# OLM-base_v0_2.net
KiCad netlist of a schematic drawn in EAGLE
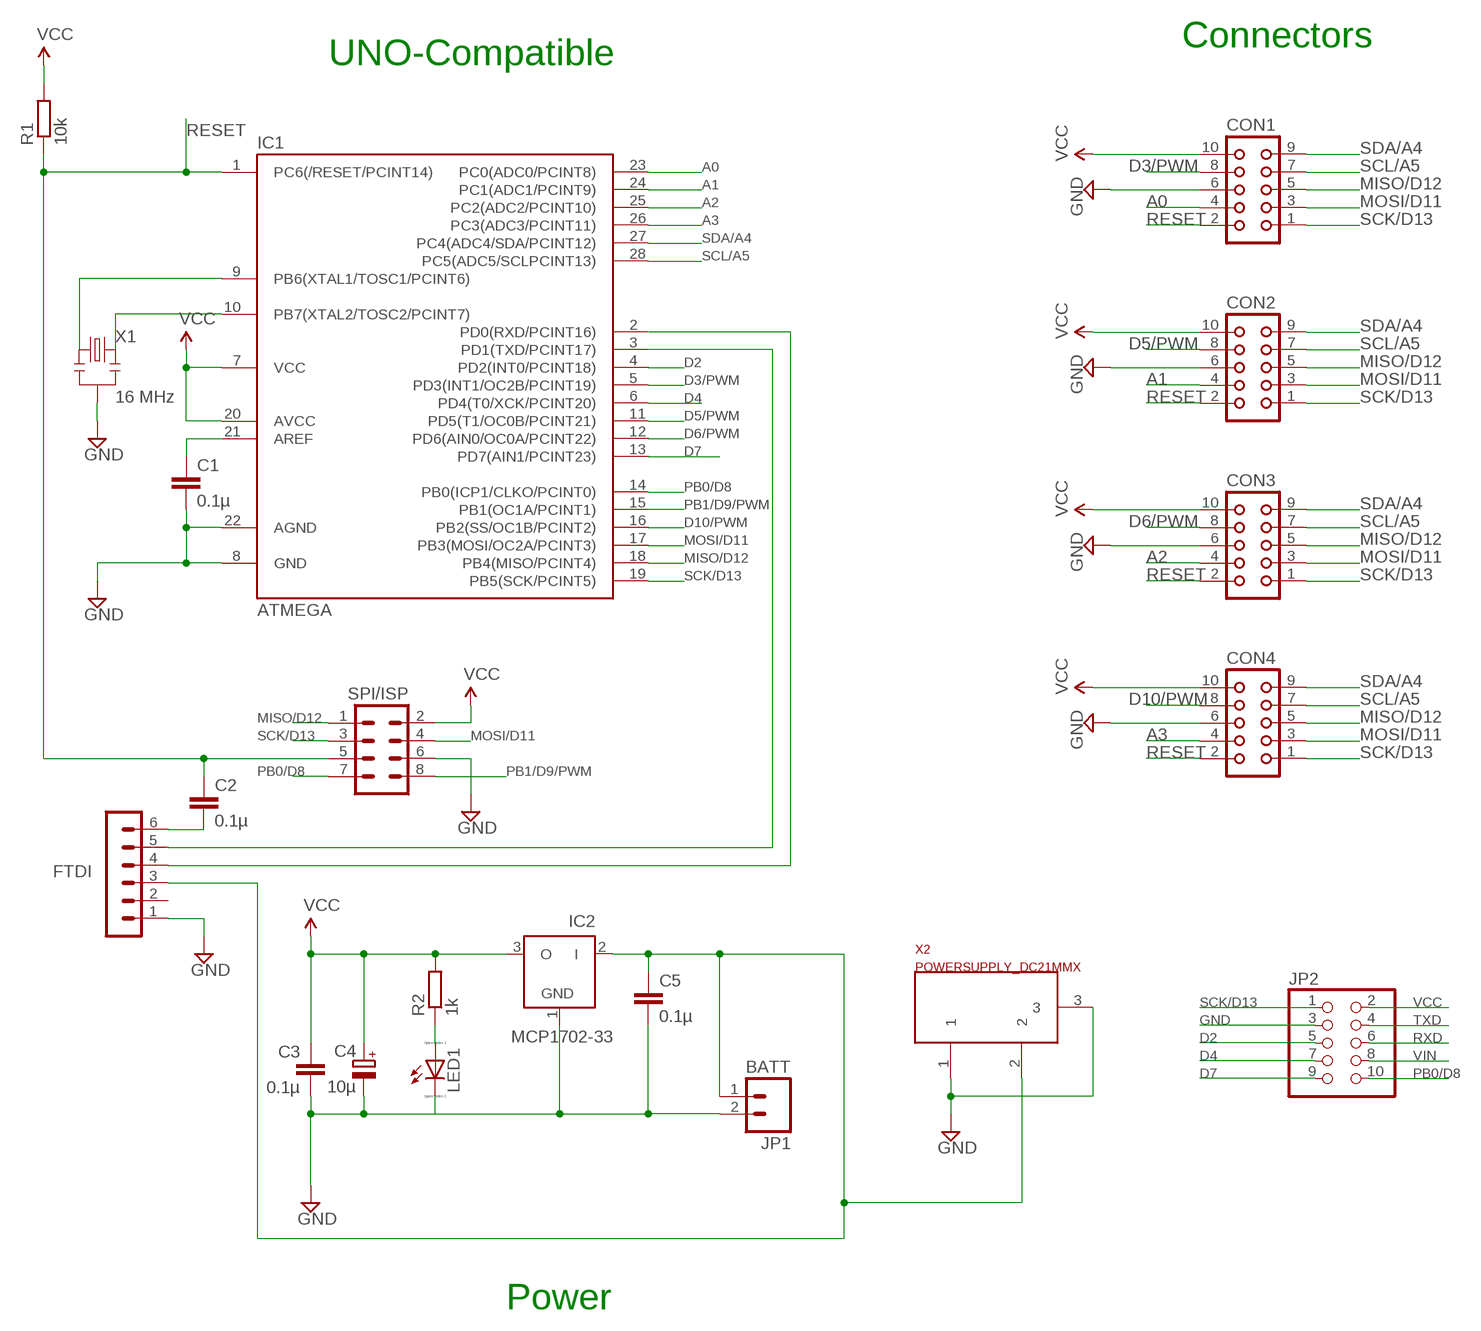
[diagram p0: schematic, sheet 1]

(export (version "E")
  (design (tool "Eeschema 10.0.6"))
  (components
    (comp (ref "C1")
      (value "0.1µ")
      (footprint "eagle-import:C025-024X044")
      (libsource (lib "eagle-import") (part "C-EU025-024X044"))
    )
    (comp (ref "C2")
      (value "0.1µ")
      (footprint "eagle-import:C025-024X044")
      (libsource (lib "eagle-import") (part "C-EU025-024X044"))
    )
    (comp (ref "C3")
      (value "0.1µ")
      (footprint "eagle-import:C025-024X044")
      (libsource (lib "eagle-import") (part "C-EU025-024X044"))
    )
    (comp (ref "C4")
      (value "10µ")
      (footprint "eagle-import:E1,8-4")
      (libsource (lib "eagle-import") (part "CPOL-EUE1.8-4"))
    )
    (comp (ref "C5")
      (value "0.1µ")
      (footprint "eagle-import:C025-024X044")
      (libsource (lib "eagle-import") (part "C-EU025-024X044"))
    )
    (comp (ref "CON1")
      (value "CON10L")
      (footprint "eagle-import:CON10L")
      (libsource (lib "eagle-import") (part "CON10L"))
    )
    (comp (ref "CON2")
      (value "CON10L")
      (footprint "eagle-import:CON10L")
      (libsource (lib "eagle-import") (part "CON10L"))
    )
    (comp (ref "CON3")
      (value "CON10L")
      (footprint "eagle-import:CON10L")
      (libsource (lib "eagle-import") (part "CON10L"))
    )
    (comp (ref "CON4")
      (value "CON10L")
      (footprint "eagle-import:CON10L")
      (libsource (lib "eagle-import") (part "CON10L"))
    )
    (comp (ref "FTDI")
      (value "FTDI")
      (footprint "eagle-import:MA06-1")
      (libsource (lib "eagle-import") (part "MA06-1"))
    )
    (comp (ref "IC1")
      (value "ATMEGA")
      (footprint "eagle-import:DIL28-3")
      (libsource (lib "eagle-import") (part "ATMEGA48/88/168-PU"))
    )
    (comp (ref "IC2")
      (value "MCP1702-33")
      (footprint "eagle-import:TO92")
      (libsource (lib "eagle-import") (part "MCP1702Z"))
    )
    (comp (ref "JP1")
      (value "BATT")
      (footprint "eagle-import:1X02_LOCK_LONGPADS")
      (libsource (lib "eagle-import") (part "M02LOCK_LONGPADS"))
    )
    (comp (ref "JP2")
      (value "PINHD-2X5")
      (footprint "eagle-import:2X05")
      (libsource (lib "eagle-import") (part "PINHD-2X5"))
    )
    (comp (ref "LED1")
      (value "LED_ELD260")
      (footprint "eagle-import:LED_LD260")
      (libsource (lib "eagle-import") (part "LED_ELD260"))
    )
    (comp (ref "R1")
      (value "10k")
      (footprint "eagle-import:0204_7")
      (libsource (lib "eagle-import") (part "R-EU_0204/7"))
    )
    (comp (ref "R2")
      (value "1k")
      (footprint "eagle-import:0204_7")
      (libsource (lib "eagle-import") (part "R-EU_0204/7"))
    )
    (comp (ref "SV1")
      (value "SPI/ISP")
      (footprint "eagle-import:MA04-2")
      (libsource (lib "eagle-import") (part "MA04-2"))
    )
    (comp (ref "X1")
      (value "16 MHz")
      (footprint "eagle-import:RESONATOR-PTH")
      (libsource (lib "eagle-import") (part "RESONATORPTH"))
    )
    (comp (ref "X2")
      (value "POWERSUPPLY_DC21MMX")
      (footprint "eagle-import:POWERSUPPLY_DC-21MM")
      (libsource (lib "eagle-import") (part "POWERSUPPLY_DC21MMX"))
    )
  )
  (nets
    (net (code "1") (name "/A0") (class "Default")
      (node (ref "CON1") (pin "4") (pinfunction "4_4") (pintype "passive"))
      (node (ref "IC1") (pin "23") (pinfunction "PC0(ADC0/PCINT8)_23") (pintype "bidirectional"))
    )
    (net (code "2") (name "/A1") (class "Default")
      (node (ref "CON2") (pin "4") (pinfunction "4_4") (pintype "passive"))
      (node (ref "IC1") (pin "24") (pinfunction "PC1(ADC1/PCINT9)_24") (pintype "bidirectional"))
    )
    (net (code "3") (name "/A2") (class "Default")
      (node (ref "CON3") (pin "4") (pinfunction "4_4") (pintype "passive"))
      (node (ref "IC1") (pin "25") (pinfunction "PC2(ADC2/PCINT10)_25") (pintype "bidirectional"))
    )
    (net (code "4") (name "/A3") (class "Default")
      (node (ref "CON4") (pin "4") (pinfunction "4_4") (pintype "passive"))
      (node (ref "IC1") (pin "26") (pinfunction "PC3(ADC3/PCINT11)_26") (pintype "bidirectional"))
    )
    (net (code "5") (name "/D2") (class "Default")
      (node (ref "IC1") (pin "4") (pinfunction "PD2(INT0/PCINT18)_4") (pintype "bidirectional"))
      (node (ref "JP2") (pin "5") (pinfunction "5_5") (pintype "passive"))
    )
    (net (code "6") (name "/D3{slash}PWM") (class "Default")
      (node (ref "CON1") (pin "8") (pinfunction "8_8") (pintype "passive"))
      (node (ref "IC1") (pin "5") (pinfunction "PD3(INT1/OC2B/PCINT19)_5") (pintype "bidirectional"))
    )
    (net (code "7") (name "/D4") (class "Default")
      (node (ref "IC1") (pin "6") (pinfunction "PD4(T0/XCK/PCINT20)_6") (pintype "bidirectional"))
      (node (ref "JP2") (pin "7") (pinfunction "7_7") (pintype "passive"))
    )
    (net (code "8") (name "/D5{slash}PWM") (class "Default")
      (node (ref "CON2") (pin "8") (pinfunction "8_8") (pintype "passive"))
      (node (ref "IC1") (pin "11") (pinfunction "PD5(T1/OC0B/PCINT21)_11") (pintype "bidirectional"))
    )
    (net (code "9") (name "/D6{slash}PWM") (class "Default")
      (node (ref "CON3") (pin "8") (pinfunction "8_8") (pintype "passive"))
      (node (ref "IC1") (pin "12") (pinfunction "PD6(AIN0/OC0A/PCINT22)_12") (pintype "bidirectional"))
    )
    (net (code "10") (name "/D7") (class "Default")
      (node (ref "IC1") (pin "13") (pinfunction "PD7(AIN1/PCINT23)_13") (pintype "bidirectional"))
      (node (ref "JP2") (pin "9") (pinfunction "9_9") (pintype "passive"))
    )
    (net (code "11") (name "/D10{slash}PWM") (class "Default")
      (node (ref "CON4") (pin "8") (pinfunction "8_8") (pintype "passive"))
      (node (ref "IC1") (pin "16") (pinfunction "PB2(SS/OC1B/PCINT2)_16") (pintype "bidirectional"))
    )
    (net (code "12") (name "/MISO{slash}D12") (class "Default")
      (node (ref "CON1") (pin "5") (pinfunction "5_5") (pintype "passive"))
      (node (ref "CON2") (pin "5") (pinfunction "5_5") (pintype "passive"))
      (node (ref "CON3") (pin "5") (pinfunction "5_5") (pintype "passive"))
      (node (ref "CON4") (pin "5") (pinfunction "5_5") (pintype "passive"))
      (node (ref "IC1") (pin "18") (pinfunction "PB4(MISO/PCINT4)_18") (pintype "bidirectional"))
      (node (ref "SV1") (pin "1") (pinfunction "1_1") (pintype "passive"))
    )
    (net (code "13") (name "/MOSI{slash}D11") (class "Default")
      (node (ref "CON1") (pin "3") (pinfunction "3_3") (pintype "passive"))
      (node (ref "CON2") (pin "3") (pinfunction "3_3") (pintype "passive"))
      (node (ref "CON3") (pin "3") (pinfunction "3_3") (pintype "passive"))
      (node (ref "CON4") (pin "3") (pinfunction "3_3") (pintype "passive"))
      (node (ref "IC1") (pin "17") (pinfunction "PB3(MOSI/OC2A/PCINT3)_17") (pintype "bidirectional"))
      (node (ref "SV1") (pin "4") (pinfunction "4_4") (pintype "passive"))
    )
    (net (code "14") (name "/PB0{slash}D8") (class "Default")
      (node (ref "IC1") (pin "14") (pinfunction "PB0(ICP1/CLKO/PCINT0)_14") (pintype "bidirectional"))
      (node (ref "JP2") (pin "10") (pinfunction "10_10") (pintype "passive"))
      (node (ref "SV1") (pin "7") (pinfunction "7_7") (pintype "passive"))
    )
    (net (code "15") (name "/PB1{slash}D9{slash}PWM") (class "Default")
      (node (ref "IC1") (pin "15") (pinfunction "PB1(OC1A/PCINT1)_15") (pintype "bidirectional"))
      (node (ref "SV1") (pin "8") (pinfunction "8_8") (pintype "passive"))
    )
    (net (code "16") (name "/RESET") (class "Default")
      (node (ref "C2") (pin "1") (pinfunction "1_1") (pintype "passive"))
      (node (ref "CON1") (pin "2") (pinfunction "2_2") (pintype "passive"))
      (node (ref "CON2") (pin "2") (pinfunction "2_2") (pintype "passive"))
      (node (ref "CON3") (pin "2") (pinfunction "2_2") (pintype "passive"))
      (node (ref "CON4") (pin "2") (pinfunction "2_2") (pintype "passive"))
      (node (ref "IC1") (pin "1") (pinfunction "PC6(/RESET/PCINT14)_1") (pintype "bidirectional"))
      (node (ref "R1") (pin "1") (pinfunction "1_1") (pintype "passive"))
      (node (ref "SV1") (pin "5") (pinfunction "5_5") (pintype "passive"))
    )
    (net (code "17") (name "/RXD") (class "Default")
      (node (ref "JP2") (pin "6") (pinfunction "6_6") (pintype "passive"))
    )
    (net (code "18") (name "/SCK{slash}D13") (class "Default")
      (node (ref "CON1") (pin "1") (pinfunction "1_1") (pintype "passive"))
      (node (ref "CON2") (pin "1") (pinfunction "1_1") (pintype "passive"))
      (node (ref "CON3") (pin "1") (pinfunction "1_1") (pintype "passive"))
      (node (ref "CON4") (pin "1") (pinfunction "1_1") (pintype "passive"))
      (node (ref "IC1") (pin "19") (pinfunction "PB5(SCK/PCINT5)_19") (pintype "bidirectional"))
      (node (ref "JP2") (pin "1") (pinfunction "1_1") (pintype "passive"))
      (node (ref "SV1") (pin "3") (pinfunction "3_3") (pintype "passive"))
    )
    (net (code "19") (name "/SCL{slash}A5") (class "Default")
      (node (ref "CON1") (pin "7") (pinfunction "7_7") (pintype "passive"))
      (node (ref "CON2") (pin "7") (pinfunction "7_7") (pintype "passive"))
      (node (ref "CON3") (pin "7") (pinfunction "7_7") (pintype "passive"))
      (node (ref "CON4") (pin "7") (pinfunction "7_7") (pintype "passive"))
      (node (ref "IC1") (pin "28") (pinfunction "PC5(ADC5/SCLPCINT13)_28") (pintype "bidirectional"))
    )
    (net (code "20") (name "/SDA{slash}A4") (class "Default")
      (node (ref "CON1") (pin "9") (pinfunction "9_9") (pintype "passive"))
      (node (ref "CON2") (pin "9") (pinfunction "9_9") (pintype "passive"))
      (node (ref "CON3") (pin "9") (pinfunction "9_9") (pintype "passive"))
      (node (ref "CON4") (pin "9") (pinfunction "9_9") (pintype "passive"))
      (node (ref "IC1") (pin "27") (pinfunction "PC4(ADC4/SDA/PCINT12)_27") (pintype "bidirectional"))
    )
    (net (code "21") (name "/TXD") (class "Default")
      (node (ref "JP2") (pin "4") (pinfunction "4_4") (pintype "passive"))
    )
    (net (code "22") (name "/VIN") (class "Default")
      (node (ref "JP2") (pin "8") (pinfunction "8_8") (pintype "passive"))
    )
    (net (code "23") (name "GND") (class "Default")
      (node (ref "C1") (pin "2") (pinfunction "2_2") (pintype "passive"))
      (node (ref "C3") (pin "2") (pinfunction "2_2") (pintype "passive"))
      (node (ref "C4") (pin "-") (pinfunction "-_-") (pintype "passive"))
      (node (ref "C5") (pin "2") (pinfunction "2_2") (pintype "passive"))
      (node (ref "CON1") (pin "6") (pinfunction "6_6") (pintype "passive"))
      (node (ref "CON2") (pin "6") (pinfunction "6_6") (pintype "passive"))
      (node (ref "CON3") (pin "6") (pinfunction "6_6") (pintype "passive"))
      (node (ref "CON4") (pin "6") (pinfunction "6_6") (pintype "passive"))
      (node (ref "FTDI") (pin "1") (pinfunction "1_1") (pintype "passive"))
      (node (ref "IC1") (pin "22") (pinfunction "AGND_22") (pintype "power_in"))
      (node (ref "IC1") (pin "8") (pinfunction "GND_8") (pintype "power_in"))
      (node (ref "IC2") (pin "1") (pinfunction "GND_1") (pintype "power_in"))
      (node (ref "JP1") (pin "2") (pinfunction "2_2") (pintype "passive"))
      (node (ref "JP2") (pin "3") (pinfunction "3_3") (pintype "passive"))
      (node (ref "SV1") (pin "6") (pinfunction "6_6") (pintype "passive"))
      (node (ref "X1") (pin "2") (pinfunction "2_2") (pintype "passive"))
      (node (ref "X2") (pin "1") (pinfunction "1_1") (pintype "power_in"))
      (node (ref "X2") (pin "3") (pinfunction "3_3") (pintype "power_in"))
    )
    (net (code "24") (name "Net-(C2-Pad2)") (class "Default")
      (node (ref "C2") (pin "2") (pinfunction "2_2") (pintype "passive"))
      (node (ref "FTDI") (pin "6") (pinfunction "6_6") (pintype "passive"))
    )
    (net (code "25") (name "Net-(IC1-AREF)") (class "Default")
      (node (ref "C1") (pin "1") (pinfunction "1_1") (pintype "passive"))
      (node (ref "IC1") (pin "21") (pinfunction "AREF_21") (pintype "passive"))
    )
    (net (code "26") (name "Net-(IC1-PB6(XTAL1{slash}TOSC1{slash}PCINT6))") (class "Default")
      (node (ref "IC1") (pin "9") (pinfunction "PB6(XTAL1/TOSC1/PCINT6)_9") (pintype "bidirectional"))
      (node (ref "X1") (pin "1") (pinfunction "1_1") (pintype "passive"))
    )
    (net (code "27") (name "Net-(IC1-PB7(XTAL2{slash}TOSC2{slash}PCINT7))") (class "Default")
      (node (ref "IC1") (pin "10") (pinfunction "PB7(XTAL2/TOSC2/PCINT7)_10") (pintype "bidirectional"))
      (node (ref "X1") (pin "3") (pinfunction "3_3") (pintype "passive"))
    )
    (net (code "28") (name "Net-(IC1-PD0(RXD{slash}PCINT16))") (class "Default")
      (node (ref "FTDI") (pin "4") (pinfunction "4_4") (pintype "passive"))
      (node (ref "IC1") (pin "2") (pinfunction "PD0(RXD/PCINT16)_2") (pintype "bidirectional"))
    )
    (net (code "29") (name "Net-(IC1-PD1(TXD{slash}PCINT17))") (class "Default")
      (node (ref "FTDI") (pin "5") (pinfunction "5_5") (pintype "passive"))
      (node (ref "IC1") (pin "3") (pinfunction "PD1(TXD/PCINT17)_3") (pintype "bidirectional"))
    )
    (net (code "30") (name "Net-(IC2-I)") (class "Default")
      (node (ref "C5") (pin "1") (pinfunction "1_1") (pintype "passive"))
      (node (ref "FTDI") (pin "3") (pinfunction "3_3") (pintype "passive"))
      (node (ref "IC2") (pin "2") (pinfunction "I_2") (pintype "input"))
      (node (ref "JP1") (pin "1") (pinfunction "1_1") (pintype "passive"))
      (node (ref "X2") (pin "2") (pinfunction "2_2") (pintype "power_in"))
    )
    (net (code "31") (name "Net-(LED1-PadA)") (class "Default")
      (node (ref "LED1") (pin "A") (pinfunction "A_A") (pintype "passive"))
      (node (ref "R2") (pin "1") (pinfunction "1_1") (pintype "passive"))
    )
    (net (code "32") (name "VCC") (class "Default")
      (node (ref "C3") (pin "1") (pinfunction "1_1") (pintype "passive"))
      (node (ref "C4") (pin "+") (pinfunction "+_+") (pintype "passive"))
      (node (ref "CON1") (pin "10") (pinfunction "10_10") (pintype "passive"))
      (node (ref "CON2") (pin "10") (pinfunction "10_10") (pintype "passive"))
      (node (ref "CON3") (pin "10") (pinfunction "10_10") (pintype "passive"))
      (node (ref "CON4") (pin "10") (pinfunction "10_10") (pintype "passive"))
      (node (ref "IC1") (pin "20") (pinfunction "AVCC_20") (pintype "passive"))
      (node (ref "IC1") (pin "7") (pinfunction "VCC_7") (pintype "power_in"))
      (node (ref "IC2") (pin "3") (pinfunction "O_3") (pintype "input"))
      (node (ref "JP2") (pin "2") (pinfunction "2_2") (pintype "passive"))
      (node (ref "R1") (pin "2") (pinfunction "2_2") (pintype "passive"))
      (node (ref "R2") (pin "2") (pinfunction "2_2") (pintype "passive"))
      (node (ref "SV1") (pin "2") (pinfunction "2_2") (pintype "passive"))
    )
    (net (code "33") (name "unconnected-(FTDI-Pad2)") (class "Default")
      (node (ref "FTDI") (pin "2") (pinfunction "2_2") (pintype "passive"))
    )
    (net (code "34") (name "unconnected-(LED1-C-PadK)") (class "Default")
      (node (ref "LED1") (pin "K") (pinfunction "C_K") (pintype "passive"))
    )
  )
)
